# Output_dig.net
KiCad netlist of a schematic drawn in Altium Designer
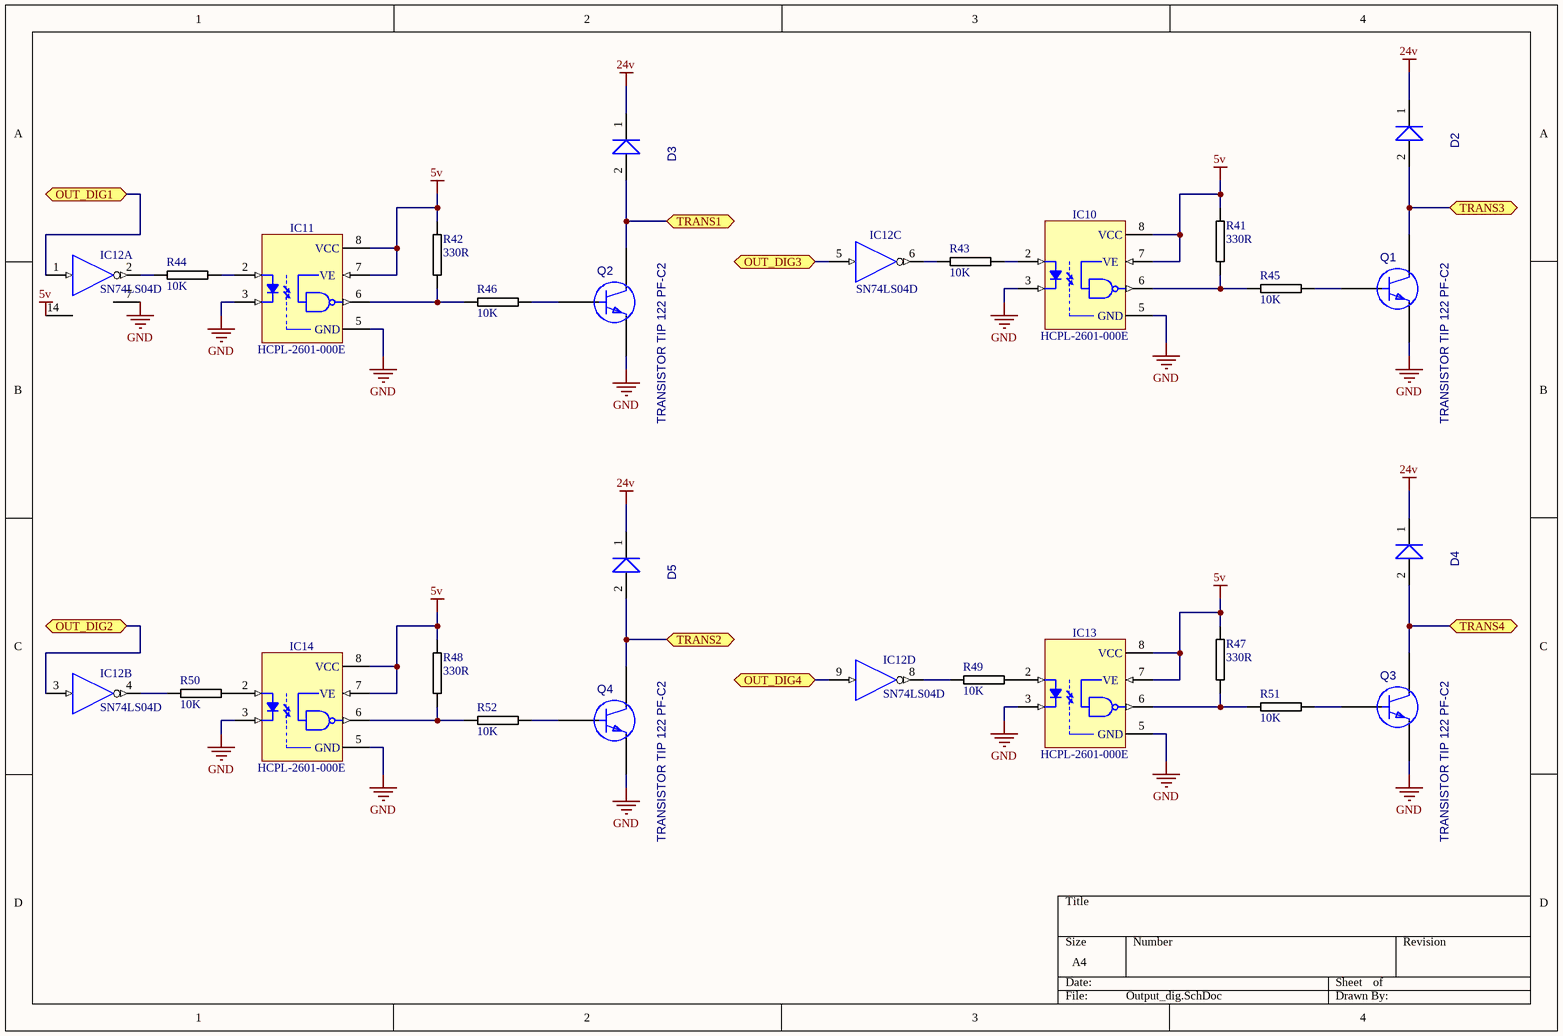
[diagram p0: Output_dig.SchDoc]

(export (version "E")
  (design (tool "Eeschema 10.0.6"))
  (components
    (comp (ref "D2")
      (value "DIODO 1N4007 PF-B1")
      (footprint "DIODO DO41 PF-B1")
      (libsource (lib "GNATUS_COMPONENTES_BASE") (part "DIODO 1N4007 PF-B1"))
    )
    (comp (ref "D3")
      (value "DIODO 1N4007 PF-B1")
      (footprint "DIODO DO41 PF-B1")
      (libsource (lib "GNATUS_COMPONENTES_BASE") (part "DIODO 1N4007 PF-B1"))
    )
    (comp (ref "D4")
      (value "DIODO 1N4007 PF-B1")
      (footprint "DIODO DO41 PF-B1")
      (libsource (lib "GNATUS_COMPONENTES_BASE") (part "DIODO 1N4007 PF-B1"))
    )
    (comp (ref "D5")
      (value "DIODO 1N4007 PF-B1")
      (footprint "DIODO DO41 PF-B1")
      (libsource (lib "GNATUS_COMPONENTES_BASE") (part "DIODO 1N4007 PF-B1"))
    )
    (comp (ref "IC10")
      (value "HCPL-2601-000E")
      (footprint "DIP8-300")
      (description "Single Optocoupler")
      (fields (field (name "MANUFACTURER") "AVAGO TECHNOLOGIES") (field (name "AUTHOR") "CERN DEM JLC"))
      (libsource (lib "ICs And Semiconductors") (part "Optocoupler Type8"))
    )
    (comp (ref "IC11")
      (value "HCPL-2601-000E")
      (footprint "DIP8-300")
      (description "Single Optocoupler")
      (fields (field (name "MANUFACTURER") "AVAGO TECHNOLOGIES") (field (name "AUTHOR") "CERN DEM JLC"))
      (libsource (lib "ICs And Semiconductors") (part "Optocoupler Type8"))
    )
    (comp (ref "IC12")
      (value "SN74LS04D")
      (footprint "SOIC127P600X175-14N")
      (description "Hex Inverter")
      (fields (field (name "MANUFACTURER") "TEXAS INSTRUMENTS") (field (name "AUTHOR") "CERN DEM JLC"))
      (libsource (lib "ICs And Semiconductors") (part "7404"))
    )
    (comp (ref "IC13")
      (value "HCPL-2601-000E")
      (footprint "DIP8-300")
      (description "Single Optocoupler")
      (fields (field (name "MANUFACTURER") "AVAGO TECHNOLOGIES") (field (name "AUTHOR") "CERN DEM JLC"))
      (libsource (lib "ICs And Semiconductors") (part "Optocoupler Type8"))
    )
    (comp (ref "IC14")
      (value "HCPL-2601-000E")
      (footprint "DIP8-300")
      (description "Single Optocoupler")
      (fields (field (name "MANUFACTURER") "AVAGO TECHNOLOGIES") (field (name "AUTHOR") "CERN DEM JLC"))
      (libsource (lib "ICs And Semiconductors") (part "Optocoupler Type8"))
    )
    (comp (ref "Q1")
      (value "TRANSISTOR TIP 122 PF-C2")
      (footprint "TRANSISTOR TO220 PF-C2")
      (libsource (lib "GNATUS_COMPONENTES_BASE") (part "TRANSISTOR TIP 122 PF-C2"))
    )
    (comp (ref "Q2")
      (value "TRANSISTOR TIP 122 PF-C2")
      (footprint "TRANSISTOR TO220 PF-C2")
      (libsource (lib "GNATUS_COMPONENTES_BASE") (part "TRANSISTOR TIP 122 PF-C2"))
    )
    (comp (ref "Q3")
      (value "TRANSISTOR TIP 122 PF-C2")
      (footprint "TRANSISTOR TO220 PF-C2")
      (libsource (lib "GNATUS_COMPONENTES_BASE") (part "TRANSISTOR TIP 122 PF-C2"))
    )
    (comp (ref "Q4")
      (value "TRANSISTOR TIP 122 PF-C2")
      (footprint "TRANSISTOR TO220 PF-C2")
      (libsource (lib "GNATUS_COMPONENTES_BASE") (part "TRANSISTOR TIP 122 PF-C2"))
    )
    (comp (ref "R41")
      (value "330R")
      (footprint "0805R-330")
      (description "RESISTOR 0805 1/4 WATT THIN FILM")
      (libsource (lib "vh_altium_library") (part "0805R-330"))
    )
    (comp (ref "R42")
      (value "330R")
      (footprint "0805R-330")
      (description "RESISTOR 0805 1/4 WATT THIN FILM")
      (libsource (lib "vh_altium_library") (part "0805R-330"))
    )
    (comp (ref "R43")
      (value "10K")
      (footprint "0805R-10K")
      (description "RESISTOR 0805 1/4 WATT THIN FILM")
      (libsource (lib "vh_altium_library") (part "0805R-10K"))
    )
    (comp (ref "R44")
      (value "10K")
      (footprint "0805R-10K")
      (description "RESISTOR 0805 1/4 WATT THIN FILM")
      (libsource (lib "vh_altium_library") (part "0805R-10K"))
    )
    (comp (ref "R45")
      (value "10K")
      (footprint "0805R-10K")
      (description "RESISTOR 0805 1/4 WATT THIN FILM")
      (libsource (lib "vh_altium_library") (part "0805R-10K"))
    )
    (comp (ref "R46")
      (value "10K")
      (footprint "0805R-10K")
      (description "RESISTOR 0805 1/4 WATT THIN FILM")
      (libsource (lib "vh_altium_library") (part "0805R-10K"))
    )
    (comp (ref "R47")
      (value "330R")
      (footprint "0805R-330")
      (description "RESISTOR 0805 1/4 WATT THIN FILM")
      (libsource (lib "vh_altium_library") (part "0805R-330"))
    )
    (comp (ref "R48")
      (value "330R")
      (footprint "0805R-330")
      (description "RESISTOR 0805 1/4 WATT THIN FILM")
      (libsource (lib "vh_altium_library") (part "0805R-330"))
    )
    (comp (ref "R49")
      (value "10K")
      (footprint "0805R-10K")
      (description "RESISTOR 0805 1/4 WATT THIN FILM")
      (libsource (lib "vh_altium_library") (part "0805R-10K"))
    )
    (comp (ref "R50")
      (value "10K")
      (footprint "0805R-10K")
      (description "RESISTOR 0805 1/4 WATT THIN FILM")
      (libsource (lib "vh_altium_library") (part "0805R-10K"))
    )
    (comp (ref "R51")
      (value "10K")
      (footprint "0805R-10K")
      (description "RESISTOR 0805 1/4 WATT THIN FILM")
      (libsource (lib "vh_altium_library") (part "0805R-10K"))
    )
    (comp (ref "R52")
      (value "10K")
      (footprint "0805R-10K")
      (description "RESISTOR 0805 1/4 WATT THIN FILM")
      (libsource (lib "vh_altium_library") (part "0805R-10K"))
    )
  )
  (nets
    (net (code "1") (name "/OUT_DIG1") (class "Default")
      (node (ref "IC12") (pin "1") (pinfunction "A_1") (pintype "input"))
    )
    (net (code "2") (name "/OUT_DIG2") (class "Default")
      (node (ref "IC12") (pin "3") (pinfunction "A_3") (pintype "passive"))
    )
    (net (code "3") (name "/OUT_DIG3") (class "Default")
      (node (ref "IC12") (pin "5") (pinfunction "A_5") (pintype "input"))
    )
    (net (code "4") (name "/OUT_DIG4") (class "Default")
      (node (ref "IC12") (pin "9") (pinfunction "A_9") (pintype "input"))
    )
    (net (code "5") (name "/TRANS1") (class "Default")
      (node (ref "D3") (pin "2") (pinfunction "A_2") (pintype "passive"))
      (node (ref "Q2") (pin "2") (pinfunction "C_2") (pintype "passive"))
    )
    (net (code "6") (name "/TRANS2") (class "Default")
      (node (ref "D5") (pin "2") (pinfunction "A_2") (pintype "passive"))
      (node (ref "Q4") (pin "2") (pinfunction "C_2") (pintype "passive"))
    )
    (net (code "7") (name "/TRANS3") (class "Default")
      (node (ref "D2") (pin "2") (pinfunction "A_2") (pintype "passive"))
      (node (ref "Q1") (pin "2") (pinfunction "C_2") (pintype "passive"))
    )
    (net (code "8") (name "/TRANS4") (class "Default")
      (node (ref "D4") (pin "2") (pinfunction "A_2") (pintype "passive"))
      (node (ref "Q3") (pin "2") (pinfunction "C_2") (pintype "passive"))
    )
    (net (code "9") (name "5v") (class "Default")
      (node (ref "IC10") (pin "7") (pinfunction "VE_7") (pintype "input"))
      (node (ref "IC10") (pin "8") (pinfunction "VCC_8") (pintype "power_in"))
      (node (ref "IC11") (pin "7") (pinfunction "VE_7") (pintype "input"))
      (node (ref "IC11") (pin "8") (pinfunction "VCC_8") (pintype "power_in"))
      (node (ref "IC12") (pin "14") (pinfunction "5v_14") (pintype "power_in"))
      (node (ref "IC13") (pin "7") (pinfunction "VE_7") (pintype "input"))
      (node (ref "IC13") (pin "8") (pinfunction "VCC_8") (pintype "power_in"))
      (node (ref "IC14") (pin "7") (pinfunction "VE_7") (pintype "input"))
      (node (ref "IC14") (pin "8") (pinfunction "VCC_8") (pintype "power_in"))
      (node (ref "R41") (pin "1") (pintype "passive"))
      (node (ref "R42") (pin "1") (pintype "passive"))
      (node (ref "R47") (pin "1") (pintype "passive"))
      (node (ref "R48") (pin "1") (pintype "passive"))
    )
    (net (code "10") (name "24v") (class "Default")
      (node (ref "D2") (pin "1") (pinfunction "K_1") (pintype "passive"))
      (node (ref "D3") (pin "1") (pinfunction "K_1") (pintype "passive"))
      (node (ref "D4") (pin "1") (pinfunction "K_1") (pintype "passive"))
      (node (ref "D5") (pin "1") (pinfunction "K_1") (pintype "passive"))
    )
    (net (code "11") (name "GND") (class "Default")
      (node (ref "IC10") (pin "3") (pinfunction "K_3") (pintype "input"))
      (node (ref "IC10") (pin "5") (pinfunction "GND_5") (pintype "power_in"))
      (node (ref "IC11") (pin "3") (pinfunction "K_3") (pintype "input"))
      (node (ref "IC11") (pin "5") (pinfunction "GND_5") (pintype "power_in"))
      (node (ref "IC12") (pin "7") (pinfunction "GND_7") (pintype "power_in"))
      (node (ref "IC13") (pin "3") (pinfunction "K_3") (pintype "input"))
      (node (ref "IC13") (pin "5") (pinfunction "GND_5") (pintype "power_in"))
      (node (ref "IC14") (pin "3") (pinfunction "K_3") (pintype "input"))
      (node (ref "IC14") (pin "5") (pinfunction "GND_5") (pintype "power_in"))
      (node (ref "Q1") (pin "3") (pinfunction "E_3") (pintype "passive"))
      (node (ref "Q2") (pin "3") (pinfunction "E_3") (pintype "passive"))
      (node (ref "Q3") (pin "3") (pinfunction "E_3") (pintype "passive"))
      (node (ref "Q4") (pin "3") (pinfunction "E_3") (pintype "passive"))
    )
    (net (code "12") (name "Net-(IC10-A)") (class "Default")
      (node (ref "IC10") (pin "2") (pinfunction "A_2") (pintype "input"))
      (node (ref "R43") (pin "2") (pintype "passive"))
    )
    (net (code "13") (name "Net-(IC10-VO)") (class "Default")
      (node (ref "IC10") (pin "6") (pinfunction "VO_6") (pintype "output"))
      (node (ref "R41") (pin "2") (pintype "passive"))
      (node (ref "R45") (pin "1") (pintype "passive"))
    )
    (net (code "14") (name "Net-(IC11-A)") (class "Default")
      (node (ref "IC11") (pin "2") (pinfunction "A_2") (pintype "input"))
      (node (ref "R44") (pin "2") (pintype "passive"))
    )
    (net (code "15") (name "Net-(IC11-VO)") (class "Default")
      (node (ref "IC11") (pin "6") (pinfunction "VO_6") (pintype "output"))
      (node (ref "R42") (pin "2") (pintype "passive"))
      (node (ref "R46") (pin "1") (pintype "passive"))
    )
    (net (code "16") (name "Net-(IC12A-~{O})") (class "Default")
      (node (ref "IC12") (pin "2") (pinfunction "~{O}_2") (pintype "output"))
      (node (ref "R44") (pin "1") (pintype "passive"))
    )
    (net (code "17") (name "Net-(IC12B-~{O})") (class "Default")
      (node (ref "IC12") (pin "4") (pinfunction "~{O}_4") (pintype "output"))
      (node (ref "R50") (pin "1") (pintype "passive"))
    )
    (net (code "18") (name "Net-(IC12C-~{O})") (class "Default")
      (node (ref "IC12") (pin "6") (pinfunction "~{O}_6") (pintype "output"))
      (node (ref "R43") (pin "1") (pintype "passive"))
    )
    (net (code "19") (name "Net-(IC12D-~{O})") (class "Default")
      (node (ref "IC12") (pin "8") (pinfunction "~{O}_8") (pintype "output"))
      (node (ref "R49") (pin "1") (pintype "passive"))
    )
    (net (code "20") (name "Net-(IC13-A)") (class "Default")
      (node (ref "IC13") (pin "2") (pinfunction "A_2") (pintype "input"))
      (node (ref "R49") (pin "2") (pintype "passive"))
    )
    (net (code "21") (name "Net-(IC13-VO)") (class "Default")
      (node (ref "IC13") (pin "6") (pinfunction "VO_6") (pintype "output"))
      (node (ref "R47") (pin "2") (pintype "passive"))
      (node (ref "R51") (pin "1") (pintype "passive"))
    )
    (net (code "22") (name "Net-(IC14-A)") (class "Default")
      (node (ref "IC14") (pin "2") (pinfunction "A_2") (pintype "input"))
      (node (ref "R50") (pin "2") (pintype "passive"))
    )
    (net (code "23") (name "Net-(IC14-VO)") (class "Default")
      (node (ref "IC14") (pin "6") (pinfunction "VO_6") (pintype "output"))
      (node (ref "R48") (pin "2") (pintype "passive"))
      (node (ref "R52") (pin "1") (pintype "passive"))
    )
    (net (code "24") (name "Net-(Q1-B)") (class "Default")
      (node (ref "Q1") (pin "1") (pinfunction "B_1") (pintype "passive"))
      (node (ref "R45") (pin "2") (pintype "passive"))
    )
    (net (code "25") (name "Net-(Q2-B)") (class "Default")
      (node (ref "Q2") (pin "1") (pinfunction "B_1") (pintype "passive"))
      (node (ref "R46") (pin "2") (pintype "passive"))
    )
    (net (code "26") (name "Net-(Q3-B)") (class "Default")
      (node (ref "Q3") (pin "1") (pinfunction "B_1") (pintype "passive"))
      (node (ref "R51") (pin "2") (pintype "passive"))
    )
    (net (code "27") (name "Net-(Q4-B)") (class "Default")
      (node (ref "Q4") (pin "1") (pinfunction "B_1") (pintype "passive"))
      (node (ref "R52") (pin "2") (pintype "passive"))
    )
    (net (code "28") (name "unconnected-(IC12B-5v-Pad14)") (class "Default")
      (node (ref "IC12") (pin "14") (pinfunction "5v_14") (pintype "power_in"))
    )
    (net (code "29") (name "unconnected-(IC12B-GND-Pad7)") (class "Default")
      (node (ref "IC12") (pin "7") (pinfunction "GND_7") (pintype "power_in"))
    )
    (net (code "30") (name "unconnected-(IC12C-5v-Pad14)") (class "Default")
      (node (ref "IC12") (pin "14") (pinfunction "5v_14") (pintype "power_in"))
    )
    (net (code "31") (name "unconnected-(IC12C-GND-Pad7)") (class "Default")
      (node (ref "IC12") (pin "7") (pinfunction "GND_7") (pintype "power_in"))
    )
    (net (code "32") (name "unconnected-(IC12D-5v-Pad14)") (class "Default")
      (node (ref "IC12") (pin "14") (pinfunction "5v_14") (pintype "power_in"))
    )
    (net (code "33") (name "unconnected-(IC12D-GND-Pad7)") (class "Default")
      (node (ref "IC12") (pin "7") (pinfunction "GND_7") (pintype "power_in"))
    )
  )
)
